# GyroAccel.net
KiCad netlist of a schematic drawn in Altium Designer
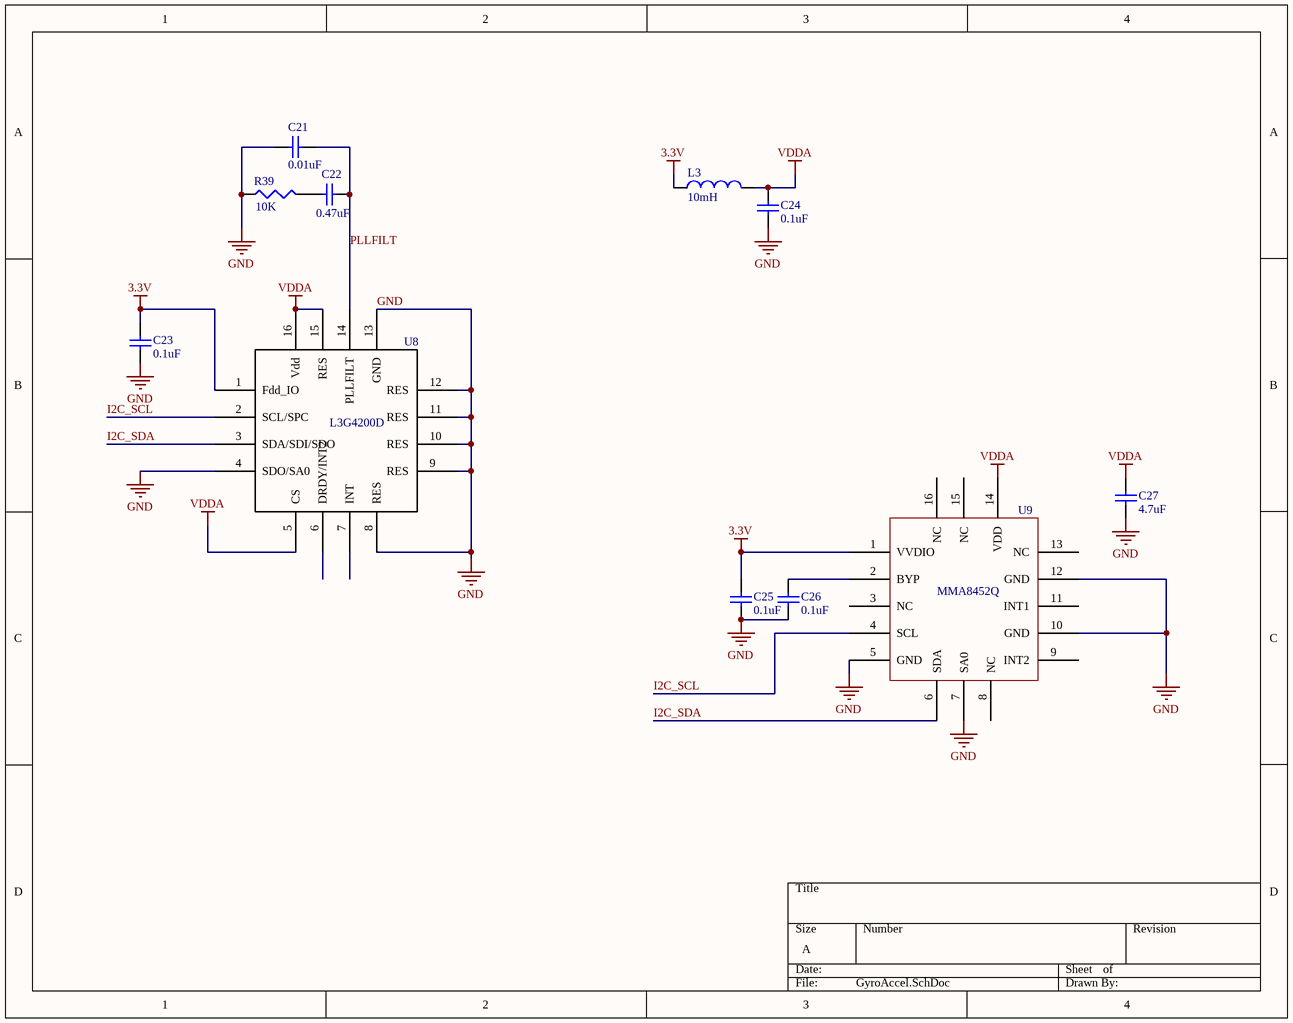
[diagram p0: GyroAccel.SchDoc]

(export (version "E")
  (design (tool "Eeschema 10.0.6"))
  (components
    (comp (ref "C21")
      (value "0.01uF")
      (footprint "CAPC1005L")
      (description "Capacitor (Semiconductor SIM Model)")
      (fields (field (name "Comment") "Cap Semi") (field (name "PUBLISHER") "Altium Limited"))
      (libsource (lib "Miscellaneous Devices") (part "Cap Semi"))
    )
    (comp (ref "C22")
      (value "0.47uF")
      (footprint "CAPC1005L")
      (description "Capacitor (Semiconductor SIM Model)")
      (fields (field (name "Comment") "Cap Semi") (field (name "PUBLISHER") "Altium Limited"))
      (libsource (lib "Miscellaneous Devices") (part "Cap Semi"))
    )
    (comp (ref "C23")
      (value "0.1uF")
      (footprint "CAPC1005L")
      (description "Capacitor (Semiconductor SIM Model)")
      (fields (field (name "Comment") "Cap Semi") (field (name "PUBLISHER") "Altium Limited"))
      (libsource (lib "Miscellaneous Devices") (part "Cap Semi"))
    )
    (comp (ref "C24")
      (value "0.1uF")
      (footprint "CAPC1005L")
      (description "Capacitor (Semiconductor SIM Model)")
      (fields (field (name "Comment") "Cap Semi") (field (name "PUBLISHER") "Altium Limited"))
      (libsource (lib "Miscellaneous Devices") (part "Cap Semi"))
    )
    (comp (ref "C25")
      (value "0.1uF")
      (footprint "CAPC1005L")
      (description "Capacitor (Semiconductor SIM Model)")
      (fields (field (name "Comment") "Cap Semi") (field (name "PUBLISHER") "Altium Limited"))
      (libsource (lib "Miscellaneous Devices") (part "Cap Semi"))
    )
    (comp (ref "C26")
      (value "0.1uF")
      (footprint "CAPC1005L")
      (description "Capacitor (Semiconductor SIM Model)")
      (fields (field (name "Comment") "Cap Semi") (field (name "PUBLISHER") "Altium Limited"))
      (libsource (lib "Miscellaneous Devices") (part "Cap Semi"))
    )
    (comp (ref "C27")
      (value "4.7uF")
      (footprint "CAPC1005L")
      (description "Capacitor (Semiconductor SIM Model)")
      (fields (field (name "Comment") "Cap Semi") (field (name "PUBLISHER") "Altium Limited"))
      (libsource (lib "Miscellaneous Devices") (part "Cap Semi"))
    )
    (comp (ref "L3")
      (value "10mH")
      (footprint "INDC2012L")
      (description "Inductor")
      (fields (field (name "PUBLISHER") "Altium Limited"))
      (libsource (lib "Miscellaneous Devices") (part "Inductor"))
    )
    (comp (ref "R39")
      (value "10K")
      (footprint "RESC1608L")
      (description "Resistor")
      (fields (field (name "Comment") "Res3") (field (name "PUBLISHER") "Altium Limited"))
      (libsource (lib "Miscellaneous Devices") (part "Res3"))
    )
    (comp (ref "U8")
      (value "L3G4200D")
      (footprint "L3G2004D")
      (description "3axis gyroscope, SPI")
      (libsource (lib "mrone") (part "L3G4200D"))
    )
    (comp (ref "U9") (value "MMA8452Q") (footprint "MMA8452Q") (libsource (lib "mrone") (part "MMA8452Q")))
  )
  (nets
    (net (code "1") (name "/I2C_SCL") (class "Default")
      (node (ref "U8") (pin "2") (pinfunction "SCL/SPC_2") (pintype "passive"))
      (node (ref "U9") (pin "4") (pinfunction "SCL_4") (pintype "passive"))
    )
    (net (code "2") (name "/I2C_SDA") (class "Default")
      (node (ref "U8") (pin "3") (pinfunction "SDA/SDI/SDO_3") (pintype "passive"))
      (node (ref "U9") (pin "6") (pinfunction "SDA_6") (pintype "passive"))
    )
    (net (code "3") (name "/PLLFILT") (class "Default")
      (node (ref "C21") (pin "1") (pinfunction "1_1") (pintype "passive"))
      (node (ref "C22") (pin "1") (pinfunction "1_1") (pintype "passive"))
      (node (ref "U8") (pin "14") (pinfunction "PLLFILT_14") (pintype "passive"))
    )
    (net (code "4") (name "3.3V") (class "Default")
      (node (ref "C23") (pin "2") (pinfunction "2_2") (pintype "passive"))
      (node (ref "C25") (pin "2") (pinfunction "2_2") (pintype "passive"))
      (node (ref "L3") (pin "2") (pinfunction "2_2") (pintype "passive"))
      (node (ref "U8") (pin "1") (pinfunction "Fdd_IO_1") (pintype "passive"))
      (node (ref "U9") (pin "1") (pinfunction "VVDIO_1") (pintype "passive"))
    )
    (net (code "5") (name "GND") (class "Default")
      (node (ref "C21") (pin "2") (pinfunction "2_2") (pintype "passive"))
      (node (ref "C23") (pin "1") (pinfunction "1_1") (pintype "passive"))
      (node (ref "C24") (pin "1") (pinfunction "1_1") (pintype "passive"))
      (node (ref "C25") (pin "1") (pinfunction "1_1") (pintype "passive"))
      (node (ref "C26") (pin "1") (pinfunction "1_1") (pintype "passive"))
      (node (ref "C27") (pin "1") (pinfunction "1_1") (pintype "passive"))
      (node (ref "R39") (pin "1") (pinfunction "1_1") (pintype "passive"))
      (node (ref "U8") (pin "10") (pinfunction "RES_10") (pintype "passive"))
      (node (ref "U8") (pin "11") (pinfunction "RES_11") (pintype "passive"))
      (node (ref "U8") (pin "12") (pinfunction "RES_12") (pintype "passive"))
      (node (ref "U8") (pin "13") (pinfunction "GND_13") (pintype "passive"))
      (node (ref "U8") (pin "4") (pinfunction "SDO/SA0_4") (pintype "passive"))
      (node (ref "U8") (pin "8") (pinfunction "RES_8") (pintype "passive"))
      (node (ref "U8") (pin "9") (pinfunction "RES_9") (pintype "passive"))
      (node (ref "U9") (pin "10") (pinfunction "GND_10") (pintype "passive"))
      (node (ref "U9") (pin "12") (pinfunction "GND_12") (pintype "passive"))
      (node (ref "U9") (pin "5") (pinfunction "GND_5") (pintype "passive"))
      (node (ref "U9") (pin "7") (pinfunction "SA0_7") (pintype "passive"))
    )
    (net (code "6") (name "Net-(C22-Pad2)") (class "Default")
      (node (ref "C22") (pin "2") (pinfunction "2_2") (pintype "passive"))
      (node (ref "R39") (pin "2") (pinfunction "2_2") (pintype "passive"))
    )
    (net (code "7") (name "Net-(U9-BYP)") (class "Default")
      (node (ref "C26") (pin "2") (pinfunction "2_2") (pintype "passive"))
      (node (ref "U9") (pin "2") (pinfunction "BYP_2") (pintype "passive"))
    )
    (net (code "8") (name "VDDA") (class "Default")
      (node (ref "C24") (pin "2") (pinfunction "2_2") (pintype "passive"))
      (node (ref "C27") (pin "2") (pinfunction "2_2") (pintype "passive"))
      (node (ref "L3") (pin "1") (pinfunction "1_1") (pintype "passive"))
      (node (ref "U8") (pin "15") (pinfunction "RES_15") (pintype "passive"))
      (node (ref "U8") (pin "16") (pinfunction "Vdd_16") (pintype "passive"))
      (node (ref "U8") (pin "5") (pinfunction "CS_5") (pintype "passive"))
      (node (ref "U9") (pin "14") (pinfunction "VDD_14") (pintype "passive"))
    )
    (net (code "9") (name "unconnected-(U8-DRDY{slash}INT2-Pad6)") (class "Default")
      (node (ref "U8") (pin "6") (pinfunction "DRDY/INT2_6") (pintype "passive"))
    )
    (net (code "10") (name "unconnected-(U8-INT-Pad7)") (class "Default")
      (node (ref "U8") (pin "7") (pinfunction "INT_7") (pintype "passive"))
    )
    (net (code "11") (name "unconnected-(U9-INT1-Pad11)") (class "Default")
      (node (ref "U9") (pin "11") (pinfunction "INT1_11") (pintype "passive"))
    )
    (net (code "12") (name "unconnected-(U9-INT2-Pad9)") (class "Default")
      (node (ref "U9") (pin "9") (pinfunction "INT2_9") (pintype "passive"))
    )
    (net (code "13") (name "unconnected-(U9-NC-Pad3)") (class "Default")
      (node (ref "U9") (pin "3") (pinfunction "NC_3") (pintype "passive"))
    )
    (net (code "14") (name "unconnected-(U9-NC-Pad8)") (class "Default")
      (node (ref "U9") (pin "8") (pinfunction "NC_8") (pintype "passive"))
    )
    (net (code "15") (name "unconnected-(U9-NC-Pad13)") (class "Default")
      (node (ref "U9") (pin "13") (pinfunction "NC_13") (pintype "passive"))
    )
    (net (code "16") (name "unconnected-(U9-NC-Pad15)") (class "Default")
      (node (ref "U9") (pin "15") (pinfunction "NC_15") (pintype "passive"))
    )
    (net (code "17") (name "unconnected-(U9-NC-Pad16)") (class "Default")
      (node (ref "U9") (pin "16") (pinfunction "NC_16") (pintype "passive"))
    )
  )
)
